# ECG_Single_Lead_board_version_6.net
KiCad netlist of a schematic drawn in EAGLE
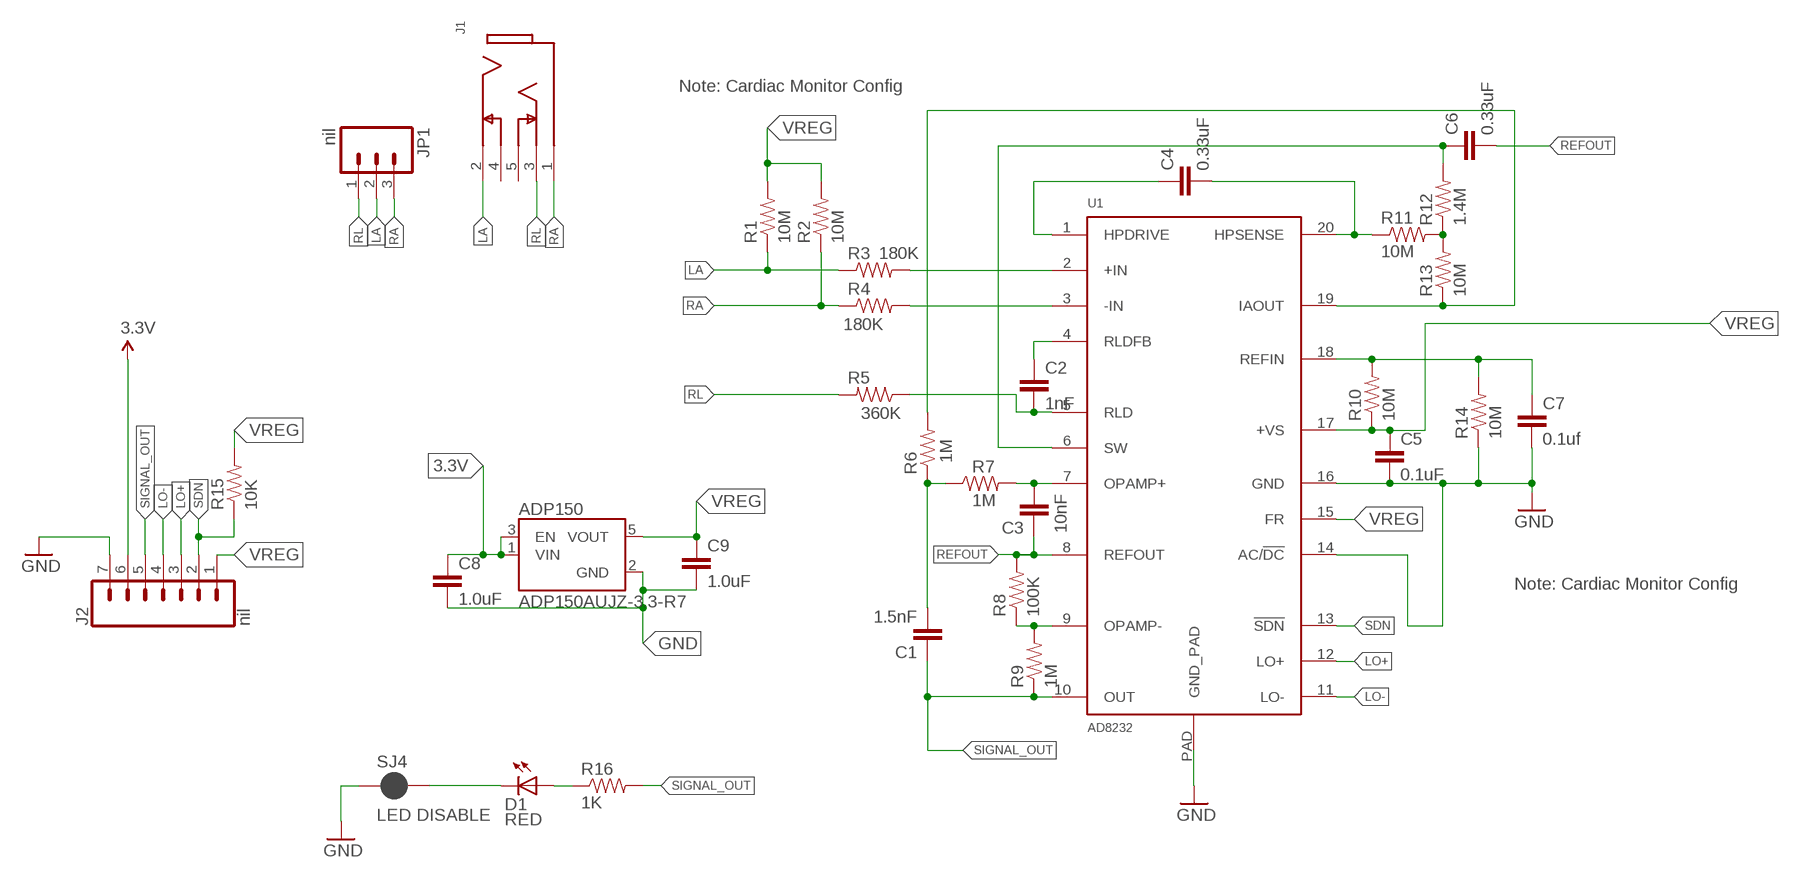
[diagram p0: schematic, sheet 1]

(export (version "E")
  (design (tool "Eeschema 10.0.6"))
  (components
    (comp (ref "ADP150")
      (value "ADP150AUJZ-3.3-R7")
      (footprint "eagle-import:SOT95P280X100-5N")
      (fields
        (field (name "DIGI-KEY_PART_NUMBER") "ADP150AUJZ-2.0-R7CT-ND")
        (field (name "MF") "Analog Devices")
        (field (name "MP") "ADP150AUJZ-2.0-R7")
      )
      (libsource (lib "eagle-import") (part "ADP150AUJZ-2.0-R7"))
    )
    (comp (ref "C1")
      (value "1.5nF")
      (footprint "eagle-import:0603-CAP")
      (libsource (lib "eagle-import") (part "CAP0603-CAP"))
    )
    (comp (ref "C2")
      (value "1nF")
      (footprint "eagle-import:0603-CAP")
      (libsource (lib "eagle-import") (part "CAP0603-CAP"))
    )
    (comp (ref "C3")
      (value "10nF")
      (footprint "eagle-import:0603-CAP")
      (libsource (lib "eagle-import") (part "CAP0603-CAP"))
    )
    (comp (ref "C4")
      (value "0.33uF")
      (footprint "eagle-import:0805")
      (libsource (lib "eagle-import") (part "CAP0805"))
    )
    (comp (ref "C5")
      (value "0.1uF")
      (footprint "eagle-import:0603-CAP")
      (libsource (lib "eagle-import") (part "CAP0603-CAP"))
    )
    (comp (ref "C6")
      (value "0.33uF")
      (footprint "eagle-import:0805")
      (libsource (lib "eagle-import") (part "CAP0805"))
    )
    (comp (ref "C7")
      (value "0.1uf")
      (footprint "eagle-import:0603-CAP")
      (libsource (lib "eagle-import") (part "CAP0603-CAP"))
    )
    (comp (ref "C8")
      (value "1.0uF")
      (footprint "eagle-import:0603")
      (libsource (lib "eagle-import") (part "1.0UF-0603-16V-10%"))
    )
    (comp (ref "C9")
      (value "1.0uF")
      (footprint "eagle-import:0603")
      (libsource (lib "eagle-import") (part "1.0UF-0603-16V-10%"))
    )
    (comp (ref "D1")
      (value "RED")
      (footprint "eagle-import:LED-0603")
      (libsource (lib "eagle-import") (part "LED-RED0603"))
    )
    (comp (ref "J1")
      (value "35RASMT4BHNTRX")
      (footprint "eagle-import:SWITCHCRAFT_35RASMT4BHNTRX")
      (fields (field (name "MF") "Switchcraft"))
      (libsource (lib "eagle-import") (part "35RASMT4BHNTRX"))
    )
    (comp (ref "J2")
      (value "nil")
      (footprint "eagle-import:1X07")
      (libsource (lib "eagle-import") (part "CONN_07"))
    )
    (comp (ref "JP1")
      (value "nil")
      (footprint "eagle-import:1X03")
      (libsource (lib "eagle-import") (part "M03PTH"))
    )
    (comp (ref "R1")
      (value "10M")
      (footprint "eagle-import:0603-RES")
      (libsource (lib "eagle-import") (part "RESISTOR0603-RES"))
    )
    (comp (ref "R2")
      (value "10M")
      (footprint "eagle-import:0603-RES")
      (libsource (lib "eagle-import") (part "RESISTOR0603-RES"))
    )
    (comp (ref "R3")
      (value "180K")
      (footprint "eagle-import:0603-RES")
      (libsource (lib "eagle-import") (part "RESISTOR0603-RES"))
    )
    (comp (ref "R4")
      (value "180K")
      (footprint "eagle-import:0603-RES")
      (libsource (lib "eagle-import") (part "RESISTOR0603-RES"))
    )
    (comp (ref "R5")
      (value "360K")
      (footprint "eagle-import:0603-RES")
      (libsource (lib "eagle-import") (part "RESISTOR0603-RES"))
    )
    (comp (ref "R6")
      (value "1M")
      (footprint "eagle-import:0603-RES")
      (libsource (lib "eagle-import") (part "RESISTOR0603-RES"))
    )
    (comp (ref "R7")
      (value "1M")
      (footprint "eagle-import:0603-RES")
      (libsource (lib "eagle-import") (part "RESISTOR0603-RES"))
    )
    (comp (ref "R8")
      (value "100K")
      (footprint "eagle-import:0603-RES")
      (libsource (lib "eagle-import") (part "RESISTOR0603-RES"))
    )
    (comp (ref "R9")
      (value "1M")
      (footprint "eagle-import:0603-RES")
      (libsource (lib "eagle-import") (part "RESISTOR0603-RES"))
    )
    (comp (ref "R10")
      (value "10M")
      (footprint "eagle-import:0603-RES")
      (libsource (lib "eagle-import") (part "RESISTOR0603-RES"))
    )
    (comp (ref "R11")
      (value "10M")
      (footprint "eagle-import:0603-RES")
      (libsource (lib "eagle-import") (part "RESISTOR0603-RES"))
    )
    (comp (ref "R12")
      (value "1.4M")
      (footprint "eagle-import:0603-RES")
      (libsource (lib "eagle-import") (part "RESISTOR0603-RES"))
    )
    (comp (ref "R13")
      (value "10M")
      (footprint "eagle-import:0603-RES")
      (libsource (lib "eagle-import") (part "RESISTOR0603-RES"))
    )
    (comp (ref "R14")
      (value "10M")
      (footprint "eagle-import:0603-RES")
      (libsource (lib "eagle-import") (part "RESISTOR0603-RES"))
    )
    (comp (ref "R15")
      (value "10K")
      (footprint "eagle-import:0603-RES")
      (libsource (lib "eagle-import") (part "10KOHM1/10W1%(0603)0603"))
    )
    (comp (ref "R16")
      (value "1K")
      (footprint "eagle-import:0603-RES")
      (libsource (lib "eagle-import") (part "1K-1%"))
    )
    (comp (ref "SJ4")
      (value "LED DISABLE")
      (footprint "eagle-import:SMT-JUMPER_2_NC_PASTE_SILK")
      (libsource (lib "eagle-import") (part "JUMPER-SMT_2_NC_PASTE_SILK"))
    )
    (comp (ref "U1")
      (value "AD8232")
      (footprint "eagle-import:LFCSP_20")
      (libsource (lib "eagle-import") (part "AD8232"))
    )
  )
  (nets
    (net (code "1") (name "3.3V") (class "Default")
      (node (ref "ADP150") (pin "1") (pinfunction "VIN_1") (pintype "input"))
      (node (ref "ADP150") (pin "3") (pinfunction "EN_3") (pintype "input"))
      (node (ref "C8") (pin "1") (pinfunction "1_1") (pintype "passive"))
      (node (ref "J2") (pin "6") (pinfunction "6_6") (pintype "passive"))
    )
    (net (code "2") (name "GND") (class "Default")
      (node (ref "ADP150") (pin "2") (pinfunction "GND_2") (pintype "power_in"))
      (node (ref "C5") (pin "2") (pinfunction "2_2") (pintype "passive"))
      (node (ref "C7") (pin "2") (pinfunction "2_2") (pintype "passive"))
      (node (ref "C8") (pin "2") (pinfunction "2_2") (pintype "passive"))
      (node (ref "C9") (pin "2") (pinfunction "2_2") (pintype "passive"))
      (node (ref "J2") (pin "7") (pinfunction "7_7") (pintype "passive"))
      (node (ref "R14") (pin "1") (pinfunction "1_1") (pintype "passive"))
      (node (ref "SJ4") (pin "1") (pinfunction "1_1") (pintype "passive"))
      (node (ref "U1") (pin "14") (pinfunction "AC/~{DC}_14") (pintype "bidirectional"))
      (node (ref "U1") (pin "16") (pinfunction "GND_16") (pintype "bidirectional"))
      (node (ref "U1") (pin "PAD") (pinfunction "GND_PAD_PAD") (pintype "bidirectional"))
    )
    (net (code "3") (name "LA") (class "Default")
      (node (ref "J1") (pin "2") (pinfunction "2_2") (pintype "passive"))
      (node (ref "JP1") (pin "2") (pinfunction "2_2") (pintype "passive"))
      (node (ref "R1") (pin "1") (pinfunction "1_1") (pintype "passive"))
      (node (ref "R3") (pin "1") (pinfunction "1_1") (pintype "passive"))
    )
    (net (code "4") (name "LO+") (class "Default")
      (node (ref "J2") (pin "3") (pinfunction "3_3") (pintype "passive"))
      (node (ref "U1") (pin "12") (pinfunction "LO+_12") (pintype "bidirectional"))
    )
    (net (code "5") (name "LO-") (class "Default")
      (node (ref "J2") (pin "4") (pinfunction "4_4") (pintype "passive"))
      (node (ref "U1") (pin "11") (pinfunction "LO-_11") (pintype "bidirectional"))
    )
    (net (code "6") (name "Net-(C1-Pad2)") (class "Default")
      (node (ref "C1") (pin "2") (pinfunction "2_2") (pintype "passive"))
      (node (ref "R6") (pin "1") (pinfunction "1_1") (pintype "passive"))
      (node (ref "R7") (pin "1") (pinfunction "1_1") (pintype "passive"))
    )
    (net (code "7") (name "Net-(D1-PadA)") (class "Default")
      (node (ref "D1") (pin "A") (pinfunction "A_A") (pintype "passive"))
      (node (ref "R16") (pin "1") (pinfunction "1_1") (pintype "passive"))
    )
    (net (code "8") (name "Net-(D1-PadC)") (class "Default")
      (node (ref "D1") (pin "C") (pinfunction "C_C") (pintype "passive"))
      (node (ref "SJ4") (pin "2") (pinfunction "2_2") (pintype "passive"))
    )
    (net (code "9") (name "Net-(R11-Pad2)") (class "Default")
      (node (ref "R11") (pin "2") (pinfunction "2_2") (pintype "passive"))
      (node (ref "R12") (pin "1") (pinfunction "1_1") (pintype "passive"))
      (node (ref "R13") (pin "2") (pinfunction "2_2") (pintype "passive"))
    )
    (net (code "10") (name "Net-(U1-+IN)") (class "Default")
      (node (ref "R3") (pin "2") (pinfunction "2_2") (pintype "passive"))
      (node (ref "U1") (pin "2") (pinfunction "+IN_2") (pintype "bidirectional"))
    )
    (net (code "11") (name "Net-(U1--IN)") (class "Default")
      (node (ref "R4") (pin "2") (pinfunction "2_2") (pintype "passive"))
      (node (ref "U1") (pin "3") (pinfunction "-IN_3") (pintype "bidirectional"))
    )
    (net (code "12") (name "Net-(U1-HPDRIVE)") (class "Default")
      (node (ref "C4") (pin "1") (pinfunction "1_1") (pintype "passive"))
      (node (ref "U1") (pin "1") (pinfunction "HPDRIVE_1") (pintype "bidirectional"))
    )
    (net (code "13") (name "Net-(U1-HPSENSE)") (class "Default")
      (node (ref "C4") (pin "2") (pinfunction "2_2") (pintype "passive"))
      (node (ref "R11") (pin "1") (pinfunction "1_1") (pintype "passive"))
      (node (ref "U1") (pin "20") (pinfunction "HPSENSE_20") (pintype "bidirectional"))
    )
    (net (code "14") (name "Net-(U1-IAOUT)") (class "Default")
      (node (ref "R13") (pin "1") (pinfunction "1_1") (pintype "passive"))
      (node (ref "R6") (pin "2") (pinfunction "2_2") (pintype "passive"))
      (node (ref "U1") (pin "19") (pinfunction "IAOUT_19") (pintype "bidirectional"))
    )
    (net (code "15") (name "Net-(U1-OPAMP+)") (class "Default")
      (node (ref "C3") (pin "2") (pinfunction "2_2") (pintype "passive"))
      (node (ref "R7") (pin "2") (pinfunction "2_2") (pintype "passive"))
      (node (ref "U1") (pin "7") (pinfunction "OPAMP+_7") (pintype "bidirectional"))
    )
    (net (code "16") (name "Net-(U1-OPAMP-)") (class "Default")
      (node (ref "R8") (pin "1") (pinfunction "1_1") (pintype "passive"))
      (node (ref "R9") (pin "2") (pinfunction "2_2") (pintype "passive"))
      (node (ref "U1") (pin "9") (pinfunction "OPAMP-_9") (pintype "bidirectional"))
    )
    (net (code "17") (name "Net-(U1-REFIN)") (class "Default")
      (node (ref "C7") (pin "1") (pinfunction "1_1") (pintype "passive"))
      (node (ref "R10") (pin "2") (pinfunction "2_2") (pintype "passive"))
      (node (ref "R14") (pin "2") (pinfunction "2_2") (pintype "passive"))
      (node (ref "U1") (pin "18") (pinfunction "REFIN_18") (pintype "bidirectional"))
    )
    (net (code "18") (name "Net-(U1-RLD)") (class "Default")
      (node (ref "C2") (pin "2") (pinfunction "2_2") (pintype "passive"))
      (node (ref "R5") (pin "1") (pinfunction "1_1") (pintype "passive"))
      (node (ref "U1") (pin "5") (pinfunction "RLD_5") (pintype "bidirectional"))
    )
    (net (code "19") (name "Net-(U1-RLDFB)") (class "Default")
      (node (ref "C2") (pin "1") (pinfunction "1_1") (pintype "passive"))
      (node (ref "U1") (pin "4") (pinfunction "RLDFB_4") (pintype "bidirectional"))
    )
    (net (code "20") (name "Net-(U1-SW)") (class "Default")
      (node (ref "C6") (pin "1") (pinfunction "1_1") (pintype "passive"))
      (node (ref "R12") (pin "2") (pinfunction "2_2") (pintype "passive"))
      (node (ref "U1") (pin "6") (pinfunction "SW_6") (pintype "bidirectional"))
    )
    (net (code "21") (name "RA") (class "Default")
      (node (ref "J1") (pin "1") (pinfunction "1_1") (pintype "passive"))
      (node (ref "JP1") (pin "3") (pinfunction "3_3") (pintype "passive"))
      (node (ref "R2") (pin "1") (pinfunction "1_1") (pintype "passive"))
      (node (ref "R4") (pin "1") (pinfunction "1_1") (pintype "passive"))
    )
    (net (code "22") (name "REFOUT") (class "Default")
      (node (ref "C3") (pin "1") (pinfunction "1_1") (pintype "passive"))
      (node (ref "C6") (pin "2") (pinfunction "2_2") (pintype "passive"))
      (node (ref "R8") (pin "2") (pinfunction "2_2") (pintype "passive"))
      (node (ref "U1") (pin "8") (pinfunction "REFOUT_8") (pintype "bidirectional"))
    )
    (net (code "23") (name "RL") (class "Default")
      (node (ref "J1") (pin "3") (pinfunction "3_3") (pintype "passive"))
      (node (ref "JP1") (pin "1") (pinfunction "1_1") (pintype "passive"))
      (node (ref "R5") (pin "2") (pinfunction "2_2") (pintype "passive"))
    )
    (net (code "24") (name "SDN") (class "Default")
      (node (ref "J2") (pin "2") (pinfunction "2_2") (pintype "passive"))
      (node (ref "R15") (pin "1") (pinfunction "1_1") (pintype "passive"))
      (node (ref "U1") (pin "13") (pinfunction "~{SDN}_13") (pintype "bidirectional"))
    )
    (net (code "25") (name "SIGNAL_OUT") (class "Default")
      (node (ref "C1") (pin "1") (pinfunction "1_1") (pintype "passive"))
      (node (ref "J2") (pin "5") (pinfunction "5_5") (pintype "passive"))
      (node (ref "R16") (pin "2") (pinfunction "2_2") (pintype "passive"))
      (node (ref "R9") (pin "1") (pinfunction "1_1") (pintype "passive"))
      (node (ref "U1") (pin "10") (pinfunction "OUT_10") (pintype "bidirectional"))
    )
    (net (code "26") (name "VREG") (class "Default")
      (node (ref "ADP150") (pin "5") (pinfunction "VOUT_5") (pintype "output"))
      (node (ref "C5") (pin "1") (pinfunction "1_1") (pintype "passive"))
      (node (ref "C9") (pin "1") (pinfunction "1_1") (pintype "passive"))
      (node (ref "J2") (pin "1") (pinfunction "1_1") (pintype "passive"))
      (node (ref "R1") (pin "2") (pinfunction "2_2") (pintype "passive"))
      (node (ref "R10") (pin "1") (pinfunction "1_1") (pintype "passive"))
      (node (ref "R15") (pin "2") (pinfunction "2_2") (pintype "passive"))
      (node (ref "R2") (pin "2") (pinfunction "2_2") (pintype "passive"))
      (node (ref "U1") (pin "15") (pinfunction "FR_15") (pintype "bidirectional"))
      (node (ref "U1") (pin "17") (pinfunction "+VS_17") (pintype "bidirectional"))
    )
    (net (code "27") (name "unconnected-(J1-Pad4)") (class "Default")
      (node (ref "J1") (pin "4") (pinfunction "4_4") (pintype "passive"))
    )
    (net (code "28") (name "unconnected-(J1-Pad5)") (class "Default")
      (node (ref "J1") (pin "5") (pinfunction "5_5") (pintype "passive"))
    )
  )
)
